# FSG_2019_BSPD_0_2_SMD.net
KiCad netlist of a schematic drawn in EAGLE
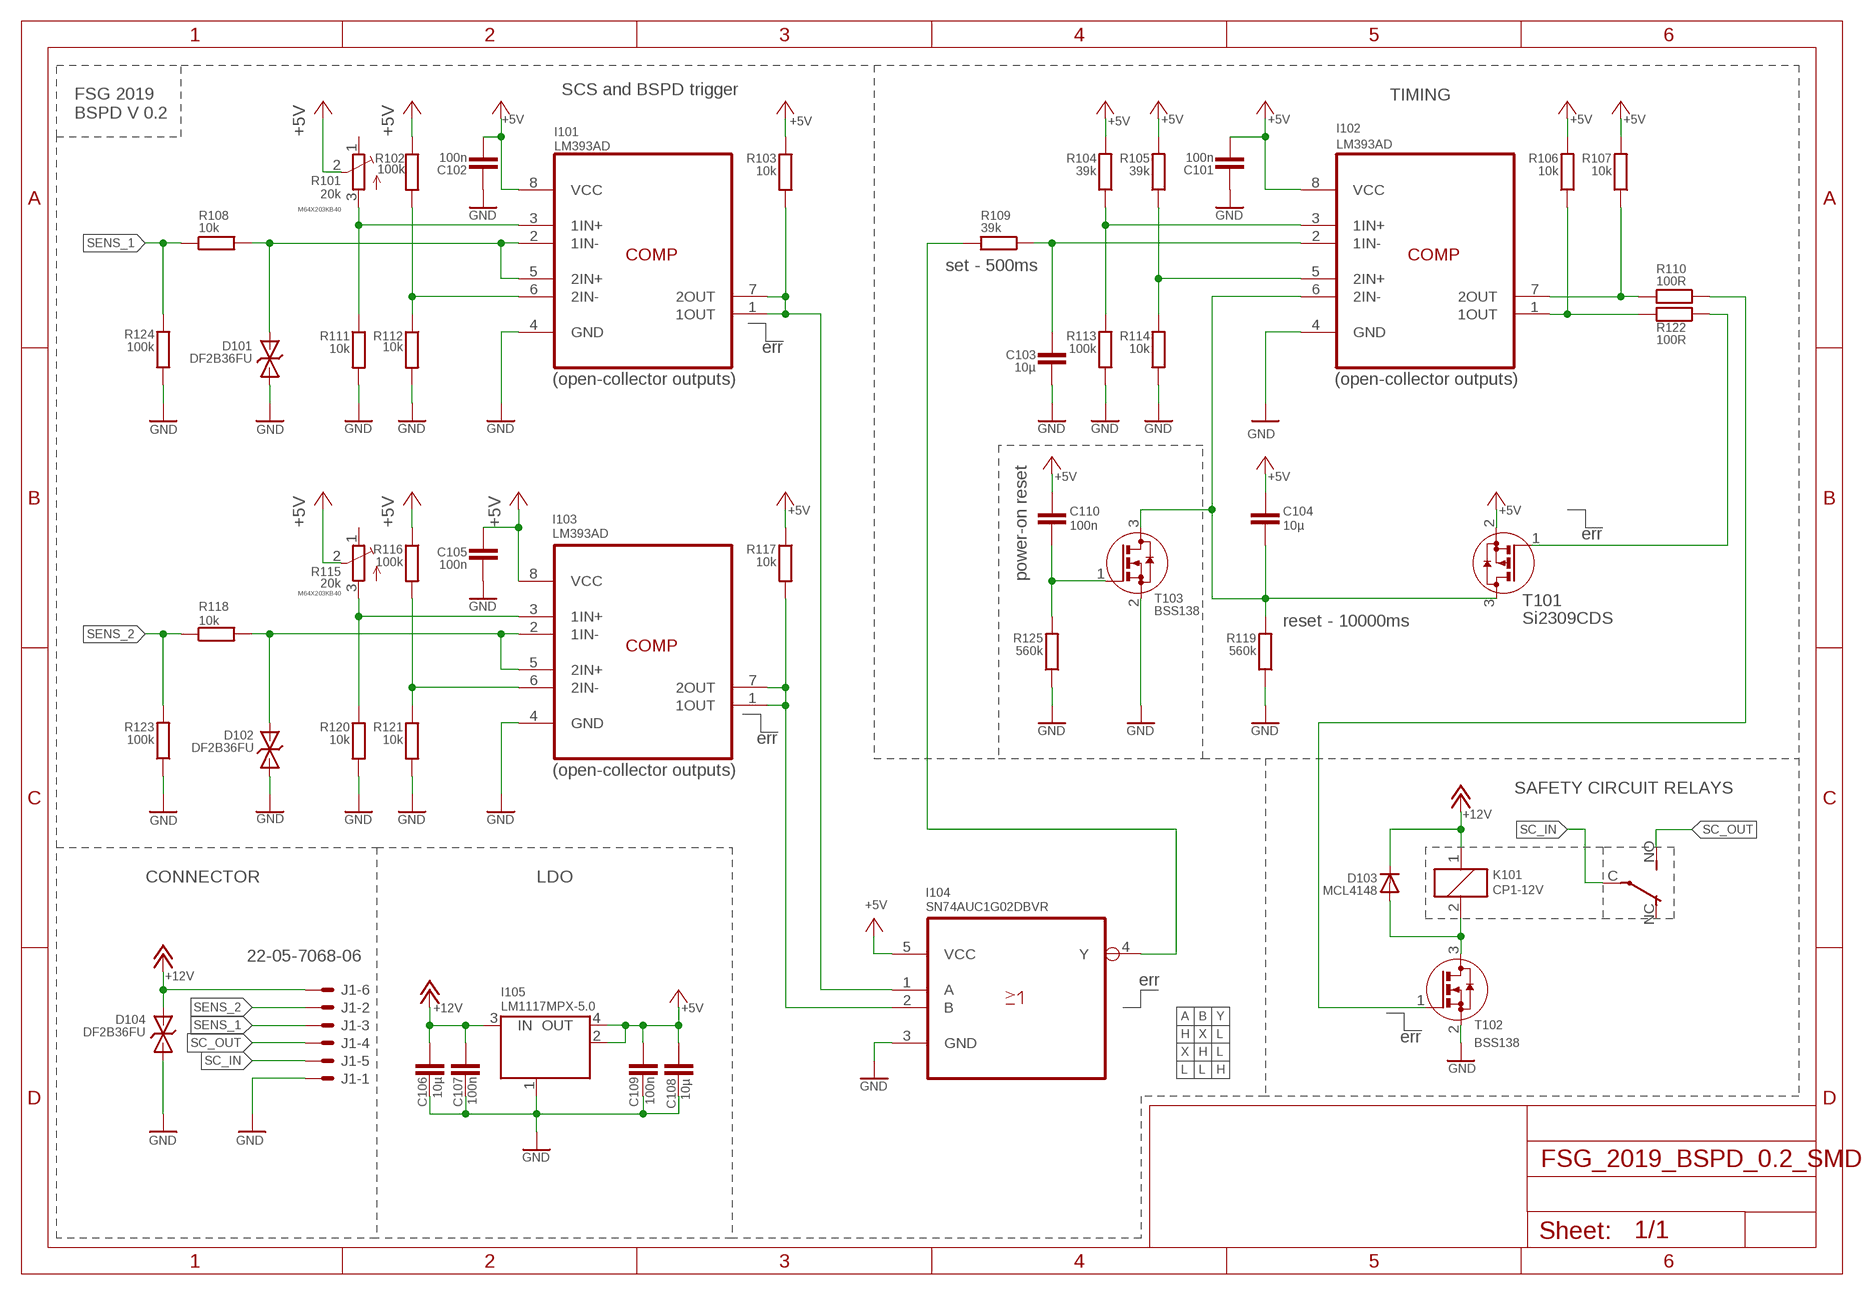
[diagram p0: schematic, sheet 1]

(export (version "E")
  (design (tool "Eeschema 10.0.6"))
  (components
    (comp (ref "C101")
      (value "100n")
      (footprint "eagle-import:C0603")
      (libsource (lib "eagle-import") (part "resistor_C-EUC0603"))
    )
    (comp (ref "C102")
      (value "100n")
      (footprint "eagle-import:C0603")
      (libsource (lib "eagle-import") (part "resistor_C-EUC0603"))
    )
    (comp (ref "C103")
      (value "10µ")
      (footprint "eagle-import:C1206")
      (libsource (lib "eagle-import") (part "C-EUC1206"))
    )
    (comp (ref "C104")
      (value "10µ")
      (footprint "eagle-import:C1206K")
      (libsource (lib "eagle-import") (part "C-EUC1206K"))
    )
    (comp (ref "C105")
      (value "100n")
      (footprint "eagle-import:C0603")
      (libsource (lib "eagle-import") (part "resistor_C-EUC0603"))
    )
    (comp (ref "C106")
      (value "10µ")
      (footprint "eagle-import:C1206")
      (libsource (lib "eagle-import") (part "C-EUC1206"))
    )
    (comp (ref "C107")
      (value "100n")
      (footprint "eagle-import:C0603")
      (libsource (lib "eagle-import") (part "C-EUC0603"))
    )
    (comp (ref "C108")
      (value "10µ")
      (footprint "eagle-import:C1206")
      (libsource (lib "eagle-import") (part "C-EUC1206"))
    )
    (comp (ref "C109")
      (value "100n")
      (footprint "eagle-import:C0603")
      (libsource (lib "eagle-import") (part "C-EUC0603"))
    )
    (comp (ref "C110")
      (value "100n")
      (footprint "eagle-import:C0603")
      (libsource (lib "eagle-import") (part "C-EUC0603"))
    )
    (comp (ref "D101")
      (value "DF2B36FU")
      (footprint "eagle-import:SOD323")
      (libsource (lib "eagle-import") (part "DF2B36FU"))
    )
    (comp (ref "D102")
      (value "DF2B36FU")
      (footprint "eagle-import:SOD323")
      (libsource (lib "eagle-import") (part "DF2B36FU"))
    )
    (comp (ref "D103")
      (value "MCL4148")
      (footprint "eagle-import:MICROMELF")
      (libsource (lib "eagle-import") (part "D.MCL4148"))
    )
    (comp (ref "D104")
      (value "DF2B36FU")
      (footprint "eagle-import:SOD323")
      (libsource (lib "eagle-import") (part "DF2B36FU"))
    )
    (comp (ref "I101")
      (value "LM393AD")
      (footprint "eagle-import:SOIC127P600X175-8N")
      (libsource (lib "eagle-import") (part "LM393AD"))
    )
    (comp (ref "I102")
      (value "LM393AD")
      (footprint "eagle-import:SOIC127P600X175-8N")
      (libsource (lib "eagle-import") (part "LM393AD"))
    )
    (comp (ref "I103")
      (value "LM393AD")
      (footprint "eagle-import:SOIC127P600X175-8N")
      (libsource (lib "eagle-import") (part "LM393AD"))
    )
    (comp (ref "I104")
      (value "SN74AUC1G02DBVR")
      (footprint "eagle-import:SOT95P280X145-5N")
      (fields (field (name "MPN") "NC7SZ08M5X"))
      (libsource (lib "eagle-import") (part "NC7SZ08M5X"))
    )
    (comp (ref "I105")
      (value "LM1117MPX-5.0")
      (footprint "eagle-import:LINEAR_SOT223")
      (fields (field (name "PART_NUMBER") "LM1117IMPX-5.0"))
      (libsource (lib "eagle-import") (part "0022_LM1117IMPX-5.0"))
    )
    (comp (ref "J1")
      (value "22-05-7068-06")
      (footprint "eagle-import:7395-06")
      (fields (field (name "MF") "MOLEX"))
      (libsource (lib "eagle-import") (part "22-?-0605-7068"))
    )
    (comp (ref "K101")
      (value "CP1-12V")
      (footprint "eagle-import:CP1")
      (fields (field (name "MF") "AROMAT/ MATSUSHITA"))
      (libsource (lib "eagle-import") (part "CP1?-12V"))
    )
    (comp (ref "R101")
      (value "20k")
      (footprint "eagle-import:M64X201KB40")
      (libsource (lib "eagle-import") (part "POTI.M64X201KB40"))
    )
    (comp (ref "R102")
      (value "100k")
      (footprint "eagle-import:R0603")
      (libsource (lib "eagle-import") (part "R-EU_R0603"))
    )
    (comp (ref "R103")
      (value "10k")
      (footprint "eagle-import:R0603")
      (libsource (lib "eagle-import") (part "R-EU_R0603"))
    )
    (comp (ref "R104")
      (value "39k")
      (footprint "eagle-import:R0603")
      (libsource (lib "eagle-import") (part "R-EU_R0603"))
    )
    (comp (ref "R105")
      (value "39k")
      (footprint "eagle-import:R0603")
      (libsource (lib "eagle-import") (part "R-EU_R0603"))
    )
    (comp (ref "R106")
      (value "10k")
      (footprint "eagle-import:R0603")
      (libsource (lib "eagle-import") (part "R-EU_R0603"))
    )
    (comp (ref "R107")
      (value "10k")
      (footprint "eagle-import:R0603")
      (libsource (lib "eagle-import") (part "R-EU_R0603"))
    )
    (comp (ref "R108")
      (value "10k")
      (footprint "eagle-import:R0603")
      (libsource (lib "eagle-import") (part "R-EU_R0603"))
    )
    (comp (ref "R109")
      (value "39k")
      (footprint "eagle-import:R0603")
      (libsource (lib "eagle-import") (part "R-EU_R0603"))
    )
    (comp (ref "R110")
      (value "100R")
      (footprint "eagle-import:R0603")
      (libsource (lib "eagle-import") (part "R-EU_R0603"))
    )
    (comp (ref "R111")
      (value "10k")
      (footprint "eagle-import:R0603")
      (libsource (lib "eagle-import") (part "R-EU_R0603"))
    )
    (comp (ref "R112")
      (value "10k")
      (footprint "eagle-import:R0603")
      (libsource (lib "eagle-import") (part "R-EU_R0603"))
    )
    (comp (ref "R113")
      (value "100k")
      (footprint "eagle-import:R0603")
      (libsource (lib "eagle-import") (part "R-EU_R0603"))
    )
    (comp (ref "R114")
      (value "10k")
      (footprint "eagle-import:R0603")
      (libsource (lib "eagle-import") (part "R-EU_R0603"))
    )
    (comp (ref "R115")
      (value "20k")
      (footprint "eagle-import:M64X201KB40")
      (libsource (lib "eagle-import") (part "POTI.M64X201KB40"))
    )
    (comp (ref "R116")
      (value "100k")
      (footprint "eagle-import:R0603")
      (libsource (lib "eagle-import") (part "R-EU_R0603"))
    )
    (comp (ref "R117")
      (value "10k")
      (footprint "eagle-import:R0603")
      (libsource (lib "eagle-import") (part "R-EU_R0603"))
    )
    (comp (ref "R118")
      (value "10k")
      (footprint "eagle-import:R0603")
      (libsource (lib "eagle-import") (part "R-EU_R0603"))
    )
    (comp (ref "R119")
      (value "560k")
      (footprint "eagle-import:R0603")
      (libsource (lib "eagle-import") (part "R-EU_R0603"))
    )
    (comp (ref "R120")
      (value "10k")
      (footprint "eagle-import:R0603")
      (libsource (lib "eagle-import") (part "R-EU_R0603"))
    )
    (comp (ref "R121")
      (value "10k")
      (footprint "eagle-import:R0603")
      (libsource (lib "eagle-import") (part "R-EU_R0603"))
    )
    (comp (ref "R122")
      (value "100R")
      (footprint "eagle-import:R0603")
      (libsource (lib "eagle-import") (part "R-EU_R0603"))
    )
    (comp (ref "R123")
      (value "100k")
      (footprint "eagle-import:R0603")
      (libsource (lib "eagle-import") (part "R-EU_R0603"))
    )
    (comp (ref "R124")
      (value "100k")
      (footprint "eagle-import:R0603")
      (libsource (lib "eagle-import") (part "R-EU_R0603"))
    )
    (comp (ref "R125")
      (value "560k")
      (footprint "eagle-import:R0603")
      (libsource (lib "eagle-import") (part "R-EU_R0603"))
    )
    (comp (ref "T101")
      (value "Si2309CDS")
      (footprint "eagle-import:SOT-23")
      (libsource (lib "eagle-import") (part "P-MOSFET.SOT23"))
    )
    (comp (ref "T102")
      (value "BSS138")
      (footprint "eagle-import:SOT-23")
      (libsource (lib "eagle-import") (part "N-MOSFET.SOT23"))
    )
    (comp (ref "T103")
      (value "BSS138")
      (footprint "eagle-import:SOT-23")
      (libsource (lib "eagle-import") (part "N-MOSFET.SOT23"))
    )
  )
  (nets
    (net (code "1") (name "+5V") (class "Default")
      (node (ref "C101") (pin "2") (pinfunction "2_2") (pintype "passive"))
      (node (ref "C102") (pin "2") (pinfunction "2_2") (pintype "passive"))
      (node (ref "C104") (pin "1") (pinfunction "1_1") (pintype "passive"))
      (node (ref "C105") (pin "2") (pinfunction "2_2") (pintype "passive"))
      (node (ref "C108") (pin "1") (pinfunction "1_1") (pintype "passive"))
      (node (ref "C109") (pin "2") (pinfunction "2_2") (pintype "passive"))
      (node (ref "C110") (pin "1") (pinfunction "1_1") (pintype "passive"))
      (node (ref "I101") (pin "8") (pinfunction "VCC_8") (pintype "power_in"))
      (node (ref "I102") (pin "8") (pinfunction "VCC_8") (pintype "power_in"))
      (node (ref "I103") (pin "8") (pinfunction "VCC_8") (pintype "power_in"))
      (node (ref "I104") (pin "5") (pinfunction "VCC_5") (pintype "power_in"))
      (node (ref "I105") (pin "2") (pinfunction "OUT_2") (pintype "passive"))
      (node (ref "I105") (pin "4") (pinfunction "OUT_4") (pintype "passive"))
      (node (ref "R101") (pin "2") (pinfunction "M_2") (pintype "passive"))
      (node (ref "R102") (pin "1") (pinfunction "1_1") (pintype "passive"))
      (node (ref "R103") (pin "1") (pinfunction "1_1") (pintype "passive"))
      (node (ref "R104") (pin "2") (pinfunction "2_2") (pintype "passive"))
      (node (ref "R105") (pin "2") (pinfunction "2_2") (pintype "passive"))
      (node (ref "R106") (pin "2") (pinfunction "2_2") (pintype "passive"))
      (node (ref "R107") (pin "2") (pinfunction "2_2") (pintype "passive"))
      (node (ref "R115") (pin "2") (pinfunction "M_2") (pintype "passive"))
      (node (ref "R116") (pin "1") (pinfunction "1_1") (pintype "passive"))
      (node (ref "R117") (pin "1") (pinfunction "1_1") (pintype "passive"))
      (node (ref "T101") (pin "2") (pinfunction "S_2") (pintype "passive"))
    )
    (net (code "2") (name "+12V") (class "Default")
      (node (ref "C106") (pin "1") (pinfunction "1_1") (pintype "passive"))
      (node (ref "C107") (pin "1") (pinfunction "1_1") (pintype "passive"))
      (node (ref "D103") (pin "C") (pinfunction "C_C") (pintype "passive"))
      (node (ref "D104") (pin "2") (pinfunction "C_2") (pintype "passive"))
      (node (ref "I105") (pin "3") (pinfunction "IN_3") (pintype "input"))
      (node (ref "J1") (pin "6") (pinfunction "S_6") (pintype "passive"))
      (node (ref "K101") (pin "1") (pinfunction "1_1") (pintype "passive"))
    )
    (net (code "3") (name "GND") (class "Default")
      (node (ref "C101") (pin "1") (pinfunction "1_1") (pintype "passive"))
      (node (ref "C102") (pin "1") (pinfunction "1_1") (pintype "passive"))
      (node (ref "C103") (pin "2") (pinfunction "2_2") (pintype "passive"))
      (node (ref "C105") (pin "1") (pinfunction "1_1") (pintype "passive"))
      (node (ref "C106") (pin "2") (pinfunction "2_2") (pintype "passive"))
      (node (ref "C107") (pin "2") (pinfunction "2_2") (pintype "passive"))
      (node (ref "C108") (pin "2") (pinfunction "2_2") (pintype "passive"))
      (node (ref "C109") (pin "1") (pinfunction "1_1") (pintype "passive"))
      (node (ref "D101") (pin "1") (pinfunction "A_1") (pintype "passive"))
      (node (ref "D102") (pin "1") (pinfunction "A_1") (pintype "passive"))
      (node (ref "D104") (pin "1") (pinfunction "A_1") (pintype "passive"))
      (node (ref "I101") (pin "4") (pinfunction "GND_4") (pintype "passive"))
      (node (ref "I102") (pin "4") (pinfunction "GND_4") (pintype "passive"))
      (node (ref "I103") (pin "4") (pinfunction "GND_4") (pintype "passive"))
      (node (ref "I104") (pin "3") (pinfunction "GND_3") (pintype "passive"))
      (node (ref "I105") (pin "1") (pinfunction "GND/ADJ_1") (pintype "input"))
      (node (ref "J1") (pin "1") (pinfunction "S_1") (pintype "passive"))
      (node (ref "R111") (pin "2") (pinfunction "2_2") (pintype "passive"))
      (node (ref "R112") (pin "2") (pinfunction "2_2") (pintype "passive"))
      (node (ref "R113") (pin "1") (pinfunction "1_1") (pintype "passive"))
      (node (ref "R114") (pin "1") (pinfunction "1_1") (pintype "passive"))
      (node (ref "R119") (pin "1") (pinfunction "1_1") (pintype "passive"))
      (node (ref "R120") (pin "2") (pinfunction "2_2") (pintype "passive"))
      (node (ref "R121") (pin "2") (pinfunction "2_2") (pintype "passive"))
      (node (ref "R123") (pin "1") (pinfunction "1_1") (pintype "passive"))
      (node (ref "R124") (pin "1") (pinfunction "1_1") (pintype "passive"))
      (node (ref "R125") (pin "1") (pinfunction "1_1") (pintype "passive"))
      (node (ref "T102") (pin "2") (pinfunction "S_2") (pintype "passive"))
      (node (ref "T103") (pin "2") (pinfunction "S_2") (pintype "passive"))
    )
    (net (code "4") (name "Net-(D101-C)") (class "Default")
      (node (ref "D101") (pin "2") (pinfunction "C_2") (pintype "passive"))
      (node (ref "I101") (pin "2") (pinfunction "1IN-_2") (pintype "input"))
      (node (ref "I101") (pin "5") (pinfunction "2IN+_5") (pintype "input"))
      (node (ref "R108") (pin "2") (pinfunction "2_2") (pintype "passive"))
    )
    (net (code "5") (name "Net-(D102-C)") (class "Default")
      (node (ref "D102") (pin "2") (pinfunction "C_2") (pintype "passive"))
      (node (ref "I103") (pin "2") (pinfunction "1IN-_2") (pintype "input"))
      (node (ref "I103") (pin "5") (pinfunction "2IN+_5") (pintype "input"))
      (node (ref "R118") (pin "2") (pinfunction "2_2") (pintype "passive"))
    )
    (net (code "6") (name "Net-(I101-1IN+)") (class "Default")
      (node (ref "I101") (pin "3") (pinfunction "1IN+_3") (pintype "input"))
      (node (ref "R101") (pin "3") (pinfunction "A_3") (pintype "passive"))
      (node (ref "R111") (pin "1") (pinfunction "1_1") (pintype "passive"))
    )
    (net (code "7") (name "Net-(I101-1OUT)") (class "Default")
      (node (ref "I101") (pin "1") (pinfunction "1OUT_1") (pintype "output"))
      (node (ref "I101") (pin "7") (pinfunction "2OUT_7") (pintype "output"))
      (node (ref "I104") (pin "1") (pinfunction "A_1") (pintype "input"))
      (node (ref "R103") (pin "2") (pinfunction "2_2") (pintype "passive"))
    )
    (net (code "8") (name "Net-(I101-2IN-)") (class "Default")
      (node (ref "I101") (pin "6") (pinfunction "2IN-_6") (pintype "input"))
      (node (ref "R102") (pin "2") (pinfunction "2_2") (pintype "passive"))
      (node (ref "R112") (pin "1") (pinfunction "1_1") (pintype "passive"))
    )
    (net (code "9") (name "Net-(I102-1IN+)") (class "Default")
      (node (ref "I102") (pin "3") (pinfunction "1IN+_3") (pintype "input"))
      (node (ref "R104") (pin "1") (pinfunction "1_1") (pintype "passive"))
      (node (ref "R113") (pin "2") (pinfunction "2_2") (pintype "passive"))
    )
    (net (code "10") (name "Net-(I102-1IN-)") (class "Default")
      (node (ref "C103") (pin "1") (pinfunction "1_1") (pintype "passive"))
      (node (ref "I102") (pin "2") (pinfunction "1IN-_2") (pintype "input"))
      (node (ref "R109") (pin "1") (pinfunction "1_1") (pintype "passive"))
    )
    (net (code "11") (name "Net-(I102-1OUT)") (class "Default")
      (node (ref "I102") (pin "1") (pinfunction "1OUT_1") (pintype "output"))
      (node (ref "R106") (pin "1") (pinfunction "1_1") (pintype "passive"))
      (node (ref "R122") (pin "2") (pinfunction "2_2") (pintype "passive"))
    )
    (net (code "12") (name "Net-(I102-2IN+)") (class "Default")
      (node (ref "I102") (pin "5") (pinfunction "2IN+_5") (pintype "input"))
      (node (ref "R105") (pin "1") (pinfunction "1_1") (pintype "passive"))
      (node (ref "R114") (pin "2") (pinfunction "2_2") (pintype "passive"))
    )
    (net (code "13") (name "Net-(I102-2IN-)") (class "Default")
      (node (ref "C104") (pin "2") (pinfunction "2_2") (pintype "passive"))
      (node (ref "I102") (pin "6") (pinfunction "2IN-_6") (pintype "input"))
      (node (ref "R119") (pin "2") (pinfunction "2_2") (pintype "passive"))
      (node (ref "T101") (pin "3") (pinfunction "D_3") (pintype "passive"))
      (node (ref "T103") (pin "3") (pinfunction "D_3") (pintype "passive"))
    )
    (net (code "14") (name "Net-(I102-2OUT)") (class "Default")
      (node (ref "I102") (pin "7") (pinfunction "2OUT_7") (pintype "output"))
      (node (ref "R107") (pin "1") (pinfunction "1_1") (pintype "passive"))
      (node (ref "R110") (pin "2") (pinfunction "2_2") (pintype "passive"))
    )
    (net (code "15") (name "Net-(I103-1IN+)") (class "Default")
      (node (ref "I103") (pin "3") (pinfunction "1IN+_3") (pintype "input"))
      (node (ref "R115") (pin "3") (pinfunction "A_3") (pintype "passive"))
      (node (ref "R120") (pin "1") (pinfunction "1_1") (pintype "passive"))
    )
    (net (code "16") (name "Net-(I103-1OUT)") (class "Default")
      (node (ref "I103") (pin "1") (pinfunction "1OUT_1") (pintype "output"))
      (node (ref "I103") (pin "7") (pinfunction "2OUT_7") (pintype "output"))
      (node (ref "I104") (pin "2") (pinfunction "B_2") (pintype "input"))
      (node (ref "R117") (pin "2") (pinfunction "2_2") (pintype "passive"))
    )
    (net (code "17") (name "Net-(I103-2IN-)") (class "Default")
      (node (ref "I103") (pin "6") (pinfunction "2IN-_6") (pintype "input"))
      (node (ref "R116") (pin "2") (pinfunction "2_2") (pintype "passive"))
      (node (ref "R121") (pin "1") (pinfunction "1_1") (pintype "passive"))
    )
    (net (code "18") (name "Net-(I104-Y)") (class "Default")
      (node (ref "I104") (pin "4") (pinfunction "Y_4") (pintype "output"))
      (node (ref "R109") (pin "2") (pinfunction "2_2") (pintype "passive"))
    )
    (net (code "19") (name "Net-(T101-G)") (class "Default")
      (node (ref "R122") (pin "1") (pinfunction "1_1") (pintype "passive"))
      (node (ref "T101") (pin "1") (pinfunction "G_1") (pintype "passive"))
    )
    (net (code "20") (name "Net-(T102-D)") (class "Default")
      (node (ref "D103") (pin "A") (pinfunction "A_A") (pintype "passive"))
      (node (ref "K101") (pin "2") (pinfunction "2_2") (pintype "passive"))
      (node (ref "T102") (pin "3") (pinfunction "D_3") (pintype "passive"))
    )
    (net (code "21") (name "Net-(T102-G)") (class "Default")
      (node (ref "R110") (pin "1") (pinfunction "1_1") (pintype "passive"))
      (node (ref "T102") (pin "1") (pinfunction "G_1") (pintype "passive"))
    )
    (net (code "22") (name "Net-(T103-G)") (class "Default")
      (node (ref "C110") (pin "2") (pinfunction "2_2") (pintype "passive"))
      (node (ref "R125") (pin "2") (pinfunction "2_2") (pintype "passive"))
      (node (ref "T103") (pin "1") (pinfunction "G_1") (pintype "passive"))
    )
    (net (code "23") (name "SC_IN") (class "Default")
      (node (ref "J1") (pin "5") (pinfunction "S_5") (pintype "passive"))
      (node (ref "K101") (pin "C") (pinfunction "P_C") (pintype "passive"))
    )
    (net (code "24") (name "SC_OUT") (class "Default")
      (node (ref "J1") (pin "4") (pinfunction "S_4") (pintype "passive"))
      (node (ref "K101") (pin "NO") (pinfunction "S_NO") (pintype "passive"))
    )
    (net (code "25") (name "SENS_1") (class "Default")
      (node (ref "J1") (pin "3") (pinfunction "S_3") (pintype "passive"))
      (node (ref "R108") (pin "1") (pinfunction "1_1") (pintype "passive"))
      (node (ref "R124") (pin "2") (pinfunction "2_2") (pintype "passive"))
    )
    (net (code "26") (name "SENS_2") (class "Default")
      (node (ref "J1") (pin "2") (pinfunction "S_2") (pintype "passive"))
      (node (ref "R118") (pin "1") (pinfunction "1_1") (pintype "passive"))
      (node (ref "R123") (pin "2") (pinfunction "2_2") (pintype "passive"))
    )
    (net (code "27") (name "unconnected-(K101B-O-PadNC)") (class "Default")
      (node (ref "K101") (pin "NC") (pinfunction "O_NC") (pintype "passive"))
    )
    (net (code "28") (name "unconnected-(R101-E-Pad1)") (class "Default")
      (node (ref "R101") (pin "1") (pinfunction "E_1") (pintype "passive"))
    )
    (net (code "29") (name "unconnected-(R115-E-Pad1)") (class "Default")
      (node (ref "R115") (pin "1") (pinfunction "E_1") (pintype "passive"))
    )
  )
)
